# dsPIC_reciver_sch.net
KiCad netlist of a schematic drawn in Altium Designer
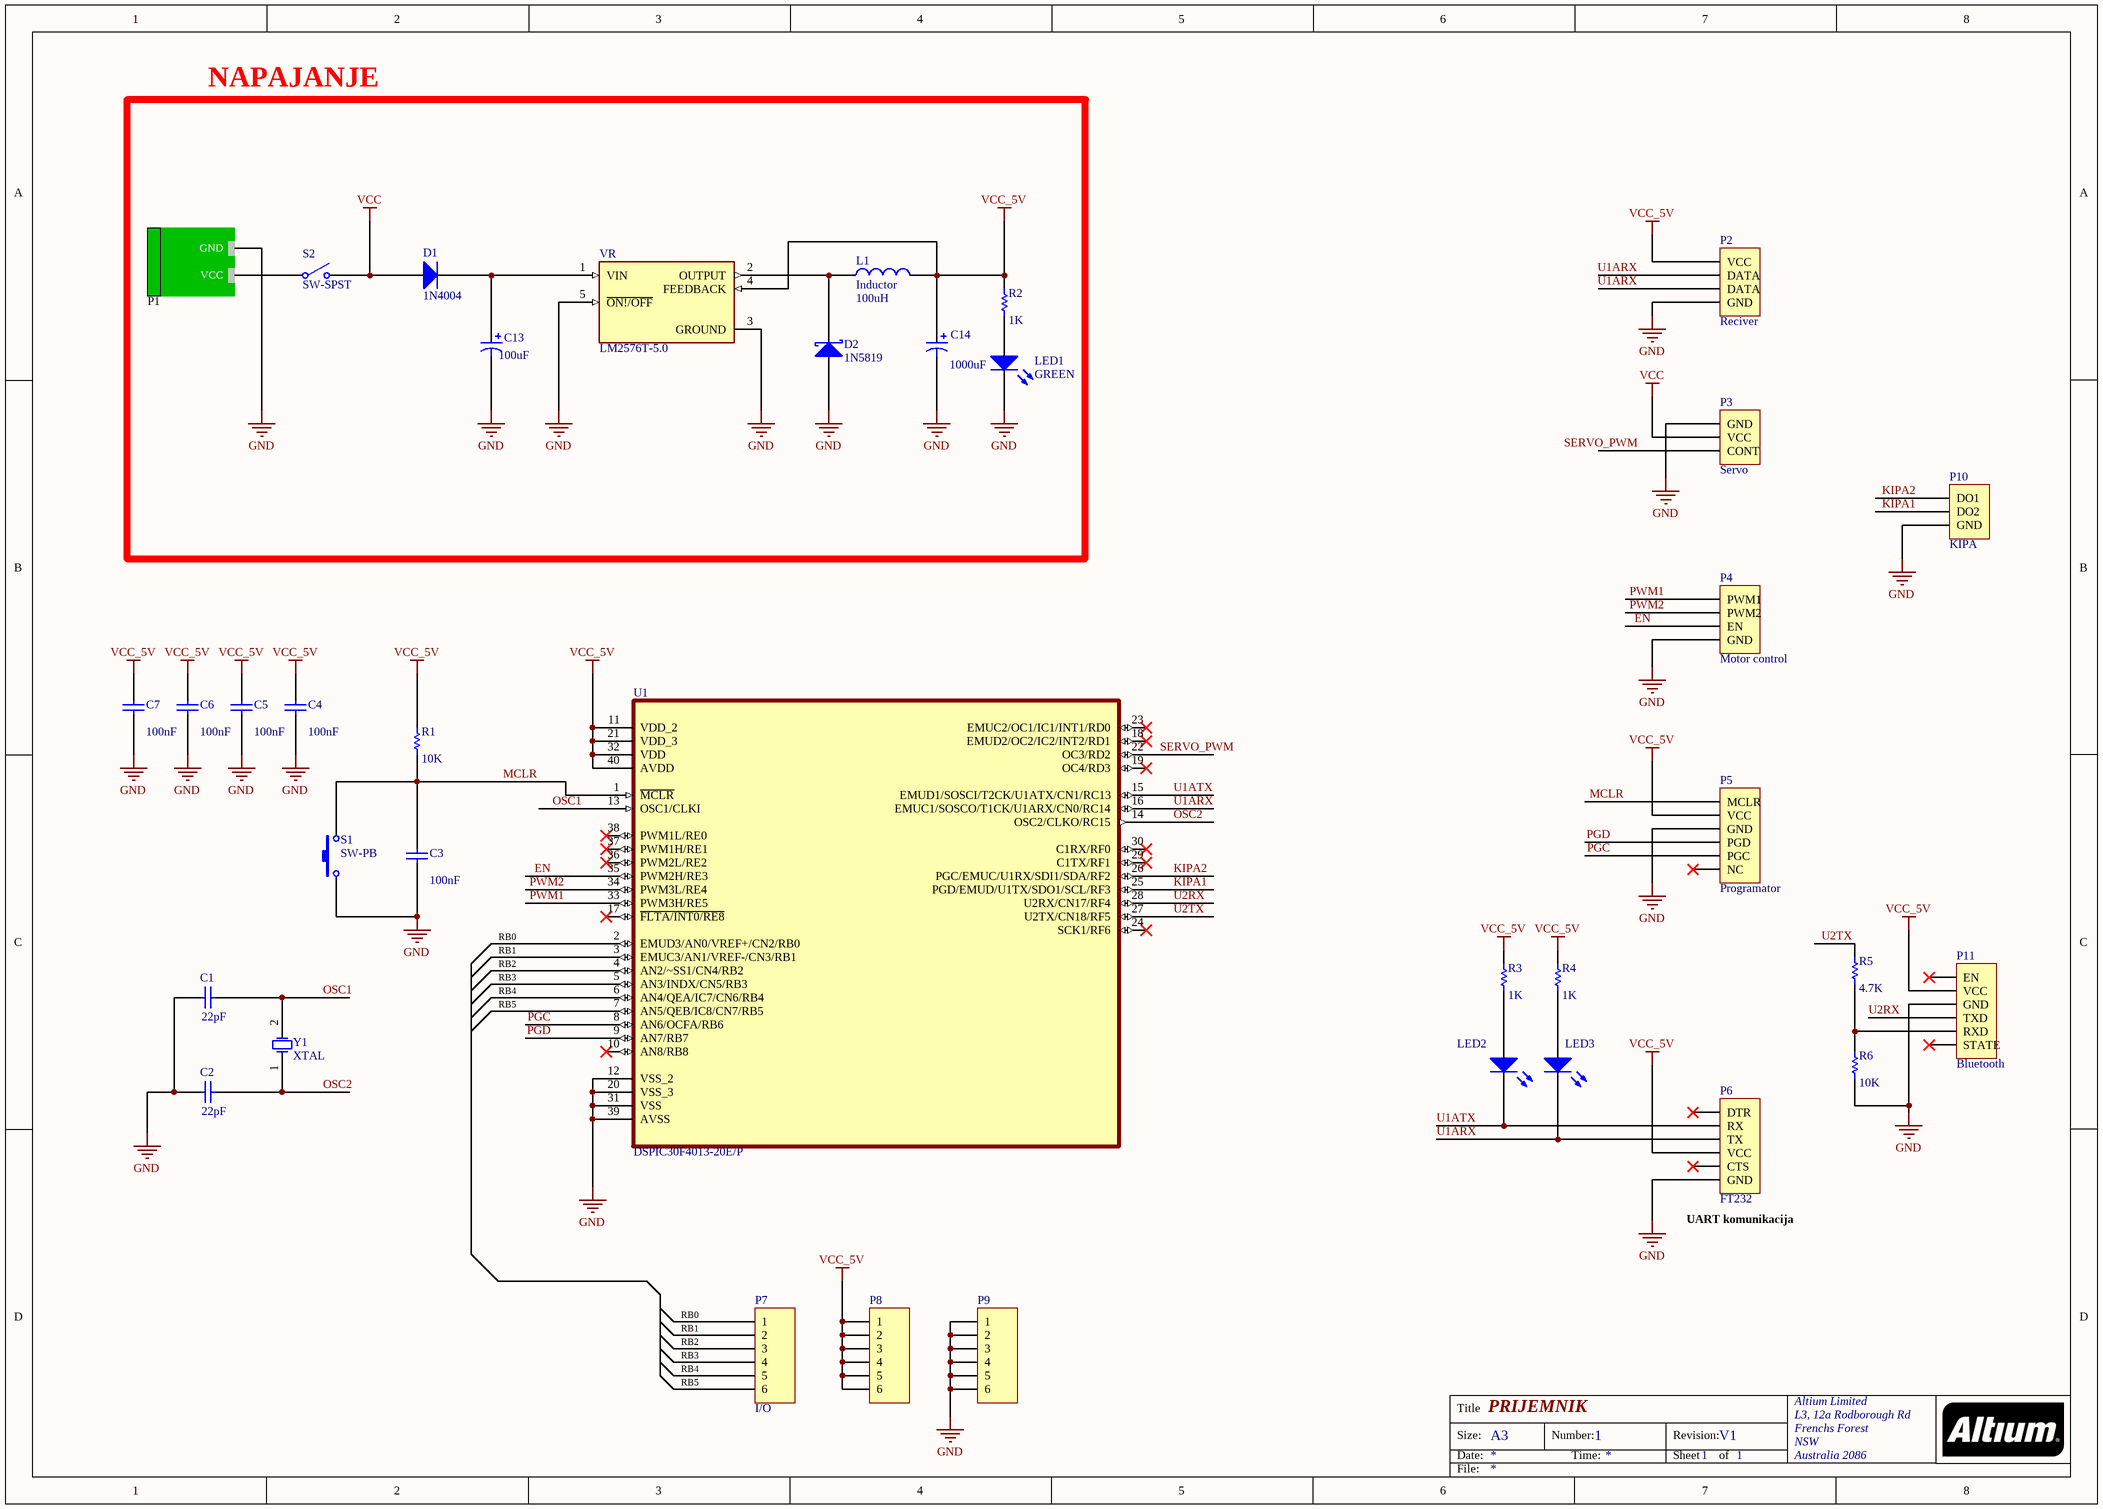
[diagram p0: dsPIC_reciver_sch.SchDoc]

(export (version "E")
  (design (tool "Eeschema 10.0.6"))
  (components
    (comp (ref "C1")
      (value "22pF")
      (footprint "CAP200")
      (description "Capacitor")
      (fields (field (name "Comment") "Cap") (field (name "PUBLISHER") "Altium Limited"))
      (libsource (lib "Miscellaneous Devices") (part "Cap"))
    )
    (comp (ref "C2")
      (value "22pF")
      (footprint "CAP200")
      (description "Capacitor")
      (fields (field (name "Comment") "Cap") (field (name "PUBLISHER") "Altium Limited"))
      (libsource (lib "Miscellaneous Devices") (part "Cap"))
    )
    (comp (ref "C3")
      (value "100nF")
      (footprint "CAP200")
      (description "Capacitor")
      (fields (field (name "Comment") "Cap") (field (name "PUBLISHER") "Altium Limited"))
      (libsource (lib "Miscellaneous Devices") (part "Cap"))
    )
    (comp (ref "C4")
      (value "100nF")
      (footprint "CAP200")
      (description "Capacitor")
      (fields (field (name "Comment") "Cap") (field (name "PUBLISHER") "Altium Limited"))
      (libsource (lib "Miscellaneous Devices") (part "Cap"))
    )
    (comp (ref "C5")
      (value "100nF")
      (footprint "CAP200")
      (description "Capacitor")
      (fields (field (name "Comment") "Cap") (field (name "PUBLISHER") "Altium Limited"))
      (libsource (lib "Miscellaneous Devices") (part "Cap"))
    )
    (comp (ref "C6")
      (value "100nF")
      (footprint "CAP200")
      (description "Capacitor")
      (fields (field (name "Comment") "Cap") (field (name "PUBLISHER") "Altium Limited"))
      (libsource (lib "Miscellaneous Devices") (part "Cap"))
    )
    (comp (ref "C7")
      (value "100nF")
      (footprint "CAP200")
      (description "Capacitor")
      (fields (field (name "Comment") "Cap") (field (name "PUBLISHER") "Altium Limited"))
      (libsource (lib "Miscellaneous Devices") (part "Cap"))
    )
    (comp (ref "C13")
      (value "100uF")
      (footprint "RAD4")
      (description "Polarized Capacitor (Radial)")
      (fields (field (name "Comment") "Cap Pol1") (field (name "PUBLISHER") "Altium Limited"))
      (libsource (lib "Miscellaneous Devices") (part "Cap Pol1"))
    )
    (comp (ref "C14")
      (value "1000uF")
      (footprint "RAD6_3")
      (description "Polarized Capacitor (Radial)")
      (fields (field (name "Comment") "Cap Pol1") (field (name "PUBLISHER") "Altium Limited"))
      (libsource (lib "Miscellaneous Devices") (part "Cap Pol1"))
    )
    (comp (ref "D1")
      (value "1N4004")
      (footprint "DIODE400")
      (description "1 Amp General Purpose Rectifier")
      (fields (field (name "PUBLISHER") "Altium Limited"))
      (libsource (lib "Miscellaneous Devices") (part "Diode 1N4004"))
    )
    (comp (ref "D2")
      (value "1N5819")
      (footprint "SDIODE300")
      (description "Schottky Diode")
      (fields (field (name "PUBLISHER") "Altium Limited"))
      (libsource (lib "Miscellaneous Devices") (part "D Schottky"))
    )
    (comp (ref "L1")
      (value "Inductor")
      (footprint "INDUCTOR_9")
      (fields (field (name "ALTIUM_VALUE") "100uH") (field (name "PUBLISHER") "Altium Limited"))
      (libsource (lib "Miscellaneous Devices") (part "Inductor"))
    )
    (comp (ref "LED1")
      (value "GREEN")
      (footprint "LED_2")
      (description "Typical RED GaAs LED")
      (fields (field (name "PUBLISHER") "Altium Limited"))
      (libsource (lib "Miscellaneous Devices") (part "LED1"))
    )
    (comp (ref "LED2")
      (value "GREEN")
      (footprint "LED_2")
      (description "Typical RED GaAs LED")
      (fields (field (name "PUBLISHER") "Altium Limited"))
      (libsource (lib "Miscellaneous Devices") (part "LED1"))
    )
    (comp (ref "LED3")
      (value "GREEN")
      (footprint "LED_2")
      (description "Typical RED GaAs LED")
      (fields (field (name "PUBLISHER") "Altium Limited"))
      (libsource (lib "Miscellaneous Devices") (part "LED1"))
    )
    (comp (ref "P1")
      (value "2EDGRC-5.08-02P-14-00A(H)")
      (footprint "PWR_Con")
      (description "TERM BLOCK HDR 2POS 90DEG 5.08MM")
      (libsource (lib "Electro_Mechanical") (part "00000002"))
    )
    (comp (ref "P2")
      (value "Reciver")
      (footprint "HEADER_4")
      (description "Header, 4-Pin")
      (fields (field (name "PUBLISHER") "Altium Limited"))
      (libsource (lib "Miscellaneous Connectors") (part "Header 4"))
    )
    (comp (ref "P3")
      (value "Servo")
      (footprint "HEADER_3")
      (description "Header, 3-Pin")
      (fields (field (name "PUBLISHER") "Altium Limited"))
      (libsource (lib "Miscellaneous Connectors") (part "Header 3"))
    )
    (comp (ref "P4")
      (value "Motor control")
      (footprint "HEADER_4")
      (description "Header, 4-Pin")
      (fields (field (name "PUBLISHER") "Altium Limited"))
      (libsource (lib "Miscellaneous Connectors") (part "Header 4"))
    )
    (comp (ref "P5")
      (value "Programator")
      (footprint "HEADER_6")
      (description "Header, 6-Pin")
      (fields (field (name "PUBLISHER") "Altium Limited"))
      (libsource (lib "Miscellaneous Connectors") (part "Header 6"))
    )
    (comp (ref "P6")
      (value "FT232")
      (footprint "HEADER_6")
      (description "Header, 6-Pin")
      (fields (field (name "PUBLISHER") "Altium Limited"))
      (libsource (lib "Miscellaneous Connectors") (part "Header 6"))
    )
    (comp (ref "P7")
      (value "I/O")
      (footprint "HEADER_6")
      (description "Header, 6-Pin")
      (fields (field (name "PUBLISHER") "Altium Limited"))
      (libsource (lib "Miscellaneous Connectors") (part "Header 6"))
    )
    (comp (ref "P8")
      (value "Header 6")
      (footprint "HEADER_6")
      (description "Header, 6-Pin")
      (fields (field (name "PUBLISHER") "Altium Limited"))
      (libsource (lib "Miscellaneous Connectors") (part "Header 6"))
    )
    (comp (ref "P9")
      (value "Header 6")
      (footprint "HEADER_6")
      (description "Header, 6-Pin")
      (fields (field (name "PUBLISHER") "Altium Limited"))
      (libsource (lib "Miscellaneous Connectors") (part "Header 6"))
    )
    (comp (ref "P10")
      (value "KIPA")
      (footprint "HEADER_3")
      (description "Header, 3-Pin")
      (fields (field (name "PUBLISHER") "Altium Limited"))
      (libsource (lib "Miscellaneous Connectors") (part "Header 3"))
    )
    (comp (ref "P11")
      (value "Bluetooth")
      (footprint "HEADER_6")
      (description "Header, 6-Pin")
      (fields (field (name "PUBLISHER") "Altium Limited"))
      (libsource (lib "Miscellaneous Connectors") (part "Header 6"))
    )
    (comp (ref "R1")
      (value "10K")
      (footprint "RES400")
      (description "Resistor")
      (fields (field (name "Comment") "Res1") (field (name "PUBLISHER") "Altium Limited"))
      (libsource (lib "Miscellaneous Devices") (part "Res1"))
    )
    (comp (ref "R2")
      (value "1K")
      (footprint "RES400")
      (description "Resistor")
      (fields (field (name "Comment") "Res1") (field (name "PUBLISHER") "Altium Limited"))
      (libsource (lib "Miscellaneous Devices") (part "Res1"))
    )
    (comp (ref "R3")
      (value "1K")
      (footprint "RES400")
      (description "Resistor")
      (fields (field (name "Comment") "Res1") (field (name "PUBLISHER") "Altium Limited"))
      (libsource (lib "Miscellaneous Devices") (part "Res1"))
    )
    (comp (ref "R4")
      (value "1K")
      (footprint "RES400")
      (description "Resistor")
      (fields (field (name "Comment") "Res1") (field (name "PUBLISHER") "Altium Limited"))
      (libsource (lib "Miscellaneous Devices") (part "Res1"))
    )
    (comp (ref "R5")
      (value "4.7K")
      (footprint "RES400")
      (description "Resistor")
      (fields (field (name "Comment") "Res1") (field (name "PUBLISHER") "Altium Limited"))
      (libsource (lib "Miscellaneous Devices") (part "Res1"))
    )
    (comp (ref "R6")
      (value "10K")
      (footprint "RES400")
      (description "Resistor")
      (fields (field (name "Comment") "Res1") (field (name "PUBLISHER") "Altium Limited"))
      (libsource (lib "Miscellaneous Devices") (part "Res1"))
    )
    (comp (ref "S1")
      (value "SW-PB")
      (footprint "SPST-2")
      (description "Switch")
      (fields (field (name "PUBLISHER") "Altium Limited"))
      (libsource (lib "Miscellaneous Devices") (part "SW-PB"))
    )
    (comp (ref "S2")
      (value "SW-SPST")
      (footprint "CAP200")
      (description "Single-Pole, Single-Throw Switch")
      (fields (field (name "PUBLISHER") "Altium Limited"))
      (libsource (lib "Miscellaneous Devices") (part "SW-SPST"))
    )
    (comp (ref "U1")
      (value "DSPIC30F4013-20E/P")
      (footprint "DIP_40")
      (description "dsPIC dsPICâ„¢ 30F Microcontroller IC 16-Bit 20 MIPS 48KB _16K x 24_ FLASH 40-PDIP")
      (fields (field (name "MF") "Microchip") (field (name "DIGI-KEY_PART_NUMBER") "DSPIC30F4013-20EP-ND"))
      (libsource (lib "DSPIC30F4013-20E_P") (part "DSPIC30F4013-20E/P"))
    )
    (comp (ref "VR")
      (value "LM2576T-5.0")
      (footprint "TO170P1067X483X1651-5")
      (description "Conv DC-DC 4V to 40V Inv/Step Down Single-Out 5V 3A 5-Pin(5+Tab) TO-220 Tube")
      (fields
        (field (name "MF") "HTC Korea")
        (field (name "BUYPART") "https://www.snapeda.com/parts/LM2576T-5.0/HTC%20Korea/view-part/4830195/?ref=eda")
      )
      (libsource (lib "LM2576T-5.0") (part "LM2576T-5.0"))
    )
    (comp (ref "Y1")
      (value "XTAL")
      (footprint "OSC_5")
      (description "Crystal Oscillator")
      (fields (field (name "PUBLISHER") "Altium Limited"))
      (libsource (lib "Miscellaneous Devices") (part "XTAL"))
    )
  )
  (nets
    (net (code "1") (name "/EN") (class "Default")
      (node (ref "P4") (pin "3") (pinfunction "DATA_3") (pintype "passive"))
      (node (ref "U1") (pin "35") (pinfunction "PWM2H/RE3_35") (pintype "bidirectional"))
    )
    (net (code "2") (name "/KIPA1") (class "Default")
      (node (ref "P10") (pin "2") (pinfunction "VCC_2") (pintype "passive"))
      (node (ref "U1") (pin "25") (pinfunction "PGD/EMUD/U1TX/SDO1/SCL/RF3_25") (pintype "bidirectional"))
    )
    (net (code "3") (name "/KIPA2") (class "Default")
      (node (ref "P10") (pin "1") (pinfunction "GND_1") (pintype "passive"))
      (node (ref "U1") (pin "26") (pinfunction "PGC/EMUC/U1RX/SDI1/SDA/RF2_26") (pintype "bidirectional"))
    )
    (net (code "4") (name "/MCLR") (class "Default")
      (node (ref "C3") (pin "2") (pinfunction "2_2") (pintype "passive"))
      (node (ref "P5") (pin "1") (pinfunction "DTR_1") (pintype "passive"))
      (node (ref "R1") (pin "1") (pinfunction "1_1") (pintype "passive"))
      (node (ref "S1") (pin "2") (pinfunction "2_2") (pintype "passive"))
      (node (ref "U1") (pin "1") (pinfunction "~{MCLR}_1") (pintype "input"))
    )
    (net (code "5") (name "/OSC1") (class "Default")
      (node (ref "C1") (pin "2") (pinfunction "2_2") (pintype "passive"))
      (node (ref "U1") (pin "13") (pinfunction "OSC1/CLKI_13") (pintype "input"))
      (node (ref "Y1") (pin "2") (pinfunction "OSC2_2") (pintype "passive"))
    )
    (net (code "6") (name "/OSC2") (class "Default")
      (node (ref "C2") (pin "2") (pinfunction "2_2") (pintype "passive"))
      (node (ref "U1") (pin "14") (pinfunction "OSC2/CLKO/RC15_14") (pintype "output"))
      (node (ref "Y1") (pin "1") (pinfunction "OSC1_1") (pintype "passive"))
    )
    (net (code "7") (name "/PGC") (class "Default")
      (node (ref "P5") (pin "5") (pinfunction "CTS_5") (pintype "passive"))
      (node (ref "U1") (pin "8") (pinfunction "AN6/OCFA/RB6_8") (pintype "bidirectional"))
    )
    (net (code "8") (name "/PGD") (class "Default")
      (node (ref "P5") (pin "4") (pinfunction "VCC_4") (pintype "passive"))
      (node (ref "U1") (pin "9") (pinfunction "AN7/RB7_9") (pintype "bidirectional"))
    )
    (net (code "9") (name "/PWM1") (class "Default")
      (node (ref "P4") (pin "1") (pinfunction "VCC_1") (pintype "passive"))
      (node (ref "U1") (pin "33") (pinfunction "PWM3H/RE5_33") (pintype "bidirectional"))
    )
    (net (code "10") (name "/PWM2") (class "Default")
      (node (ref "P4") (pin "2") (pinfunction "DATA_2") (pintype "passive"))
      (node (ref "U1") (pin "34") (pinfunction "PWM3L/RE4_34") (pintype "bidirectional"))
    )
    (net (code "11") (name "/RB0") (class "Default")
      (node (ref "P7") (pin "1") (pinfunction "DTR_1") (pintype "passive"))
      (node (ref "U1") (pin "2") (pinfunction "EMUD3/AN0/VREF+/CN2/RB0_2") (pintype "bidirectional"))
    )
    (net (code "12") (name "/RB1") (class "Default")
      (node (ref "P7") (pin "2") (pinfunction "RX_2") (pintype "passive"))
      (node (ref "U1") (pin "3") (pinfunction "EMUC3/AN1/VREF-/CN3/RB1_3") (pintype "bidirectional"))
    )
    (net (code "13") (name "/RB2") (class "Default")
      (node (ref "P7") (pin "3") (pinfunction "TX_3") (pintype "passive"))
      (node (ref "U1") (pin "4") (pinfunction "AN2/~SS1/CN4/RB2_4") (pintype "bidirectional"))
    )
    (net (code "14") (name "/RB3") (class "Default")
      (node (ref "P7") (pin "4") (pinfunction "VCC_4") (pintype "passive"))
      (node (ref "U1") (pin "5") (pinfunction "AN3/INDX/CN5/RB3_5") (pintype "bidirectional"))
    )
    (net (code "15") (name "/RB4") (class "Default")
      (node (ref "P7") (pin "5") (pinfunction "CTS_5") (pintype "passive"))
      (node (ref "U1") (pin "6") (pinfunction "AN4/QEA/IC7/CN6/RB4_6") (pintype "bidirectional"))
    )
    (net (code "16") (name "/RB5") (class "Default")
      (node (ref "P7") (pin "6") (pinfunction "GND_6") (pintype "passive"))
      (node (ref "U1") (pin "7") (pinfunction "AN5/QEB/IC8/CN7/RB5_7") (pintype "bidirectional"))
    )
    (net (code "17") (name "/SERVO_PWM") (class "Default")
      (node (ref "P3") (pin "3") (pinfunction "CONT_3") (pintype "passive"))
      (node (ref "U1") (pin "22") (pinfunction "OC3/RD2_22") (pintype "bidirectional"))
    )
    (net (code "18") (name "/U1ARX") (class "Default")
      (node (ref "LED3") (pin "2") (pinfunction "K_2") (pintype "passive"))
      (node (ref "P2") (pin "2") (pinfunction "DATA_2") (pintype "passive"))
      (node (ref "P2") (pin "3") (pinfunction "DATA_3") (pintype "passive"))
      (node (ref "P6") (pin "3") (pinfunction "TX_3") (pintype "passive"))
      (node (ref "U1") (pin "16") (pinfunction "EMUC1/SOSCO/T1CK/U1ARX/CN0/RC14_16") (pintype "bidirectional"))
    )
    (net (code "19") (name "/U1ATX") (class "Default")
      (node (ref "LED2") (pin "2") (pinfunction "K_2") (pintype "passive"))
      (node (ref "P6") (pin "2") (pinfunction "RX_2") (pintype "passive"))
      (node (ref "U1") (pin "15") (pinfunction "EMUD1/SOSCI/T2CK/U1ATX/CN1/RC13_15") (pintype "bidirectional"))
    )
    (net (code "20") (name "/U2RX") (class "Default")
      (node (ref "P11") (pin "4") (pinfunction "VCC_4") (pintype "passive"))
      (node (ref "U1") (pin "28") (pinfunction "U2RX/CN17/RF4_28") (pintype "bidirectional"))
    )
    (net (code "21") (name "/U2TX") (class "Default")
      (node (ref "R5") (pin "2") (pinfunction "2_2") (pintype "passive"))
      (node (ref "U1") (pin "27") (pinfunction "U2TX/CN18/RF5_27") (pintype "bidirectional"))
    )
    (net (code "22") (name "GND") (class "Default")
      (node (ref "C1") (pin "1") (pinfunction "1_1") (pintype "passive"))
      (node (ref "C13") (pin "2") (pinfunction "2_2") (pintype "passive"))
      (node (ref "C14") (pin "2") (pinfunction "2_2") (pintype "passive"))
      (node (ref "C2") (pin "1") (pinfunction "1_1") (pintype "passive"))
      (node (ref "C3") (pin "1") (pinfunction "1_1") (pintype "passive"))
      (node (ref "C4") (pin "1") (pinfunction "1_1") (pintype "passive"))
      (node (ref "C5") (pin "1") (pinfunction "1_1") (pintype "passive"))
      (node (ref "C6") (pin "1") (pinfunction "1_1") (pintype "passive"))
      (node (ref "C7") (pin "1") (pinfunction "1_1") (pintype "passive"))
      (node (ref "D2") (pin "1") (pinfunction "A_1") (pintype "passive"))
      (node (ref "LED1") (pin "2") (pinfunction "K_2") (pintype "passive"))
      (node (ref "P1") (pin "1") (pinfunction "GND_1") (pintype "passive"))
      (node (ref "P10") (pin "3") (pinfunction "CONT_3") (pintype "passive"))
      (node (ref "P11") (pin "3") (pinfunction "TX_3") (pintype "passive"))
      (node (ref "P2") (pin "4") (pinfunction "GND_4") (pintype "passive"))
      (node (ref "P3") (pin "1") (pinfunction "GND_1") (pintype "passive"))
      (node (ref "P4") (pin "4") (pinfunction "GND_4") (pintype "passive"))
      (node (ref "P5") (pin "3") (pinfunction "TX_3") (pintype "passive"))
      (node (ref "P6") (pin "6") (pinfunction "GND_6") (pintype "passive"))
      (node (ref "P9") (pin "1") (pinfunction "DTR_1") (pintype "passive"))
      (node (ref "P9") (pin "2") (pinfunction "RX_2") (pintype "passive"))
      (node (ref "P9") (pin "3") (pinfunction "TX_3") (pintype "passive"))
      (node (ref "P9") (pin "4") (pinfunction "VCC_4") (pintype "passive"))
      (node (ref "P9") (pin "5") (pinfunction "CTS_5") (pintype "passive"))
      (node (ref "P9") (pin "6") (pinfunction "GND_6") (pintype "passive"))
      (node (ref "R6") (pin "1") (pinfunction "1_1") (pintype "passive"))
      (node (ref "S1") (pin "1") (pinfunction "1_1") (pintype "passive"))
      (node (ref "U1") (pin "12") (pinfunction "VSS_2_12") (pintype "power_in"))
      (node (ref "U1") (pin "20") (pinfunction "VSS_3_20") (pintype "power_in"))
      (node (ref "U1") (pin "31") (pinfunction "VSS_31") (pintype "power_in"))
      (node (ref "U1") (pin "39") (pinfunction "AVSS_39") (pintype "power_in"))
      (node (ref "VR") (pin "3") (pinfunction "GROUND_3") (pintype "power_in"))
      (node (ref "VR") (pin "5") (pinfunction "~{ON!/OFF}_5") (pintype "input"))
    )
    (net (code "23") (name "Net-(D1-K)") (class "Default")
      (node (ref "C13") (pin "1") (pinfunction "1_1") (pintype "passive"))
      (node (ref "D1") (pin "2") (pinfunction "K_2") (pintype "passive"))
      (node (ref "VR") (pin "1") (pinfunction "VIN_1") (pintype "input"))
    )
    (net (code "24") (name "Net-(D2-K)") (class "Default")
      (node (ref "D2") (pin "2") (pinfunction "K_2") (pintype "passive"))
      (node (ref "L1") (pin "1") (pinfunction "1_1") (pintype "passive"))
      (node (ref "VR") (pin "2") (pinfunction "OUTPUT_2") (pintype "output"))
    )
    (net (code "25") (name "Net-(LED1-A)") (class "Default")
      (node (ref "LED1") (pin "1") (pinfunction "A_1") (pintype "passive"))
      (node (ref "R2") (pin "1") (pinfunction "1_1") (pintype "passive"))
    )
    (net (code "26") (name "Net-(LED2-A)") (class "Default")
      (node (ref "LED2") (pin "1") (pinfunction "A_1") (pintype "passive"))
      (node (ref "R3") (pin "1") (pinfunction "1_1") (pintype "passive"))
    )
    (net (code "27") (name "Net-(LED3-A)") (class "Default")
      (node (ref "LED3") (pin "1") (pinfunction "A_1") (pintype "passive"))
      (node (ref "R4") (pin "1") (pinfunction "1_1") (pintype "passive"))
    )
    (net (code "28") (name "Net-(P1-VCC)") (class "Default")
      (node (ref "P1") (pin "2") (pinfunction "VCC_2") (pintype "passive"))
      (node (ref "S2") (pin "1") (pinfunction "COMMON_1") (pintype "passive"))
    )
    (net (code "29") (name "Net-(P11-CTS)") (class "Default")
      (node (ref "P11") (pin "5") (pinfunction "CTS_5") (pintype "passive"))
      (node (ref "R5") (pin "1") (pinfunction "1_1") (pintype "passive"))
      (node (ref "R6") (pin "2") (pinfunction "2_2") (pintype "passive"))
    )
    (net (code "30") (name "VCC") (class "Default")
      (node (ref "D1") (pin "1") (pinfunction "A_1") (pintype "passive"))
      (node (ref "P3") (pin "2") (pinfunction "VCC_2") (pintype "passive"))
      (node (ref "S2") (pin "2") (pinfunction "NO_2") (pintype "passive"))
    )
    (net (code "31") (name "VCC_5V") (class "Default")
      (node (ref "C14") (pin "1") (pinfunction "1_1") (pintype "passive"))
      (node (ref "C4") (pin "2") (pinfunction "2_2") (pintype "passive"))
      (node (ref "C5") (pin "2") (pinfunction "2_2") (pintype "passive"))
      (node (ref "C6") (pin "2") (pinfunction "2_2") (pintype "passive"))
      (node (ref "C7") (pin "2") (pinfunction "2_2") (pintype "passive"))
      (node (ref "L1") (pin "2") (pinfunction "2_2") (pintype "passive"))
      (node (ref "P11") (pin "2") (pinfunction "RX_2") (pintype "passive"))
      (node (ref "P2") (pin "1") (pinfunction "VCC_1") (pintype "passive"))
      (node (ref "P5") (pin "2") (pinfunction "RX_2") (pintype "passive"))
      (node (ref "P6") (pin "4") (pinfunction "VCC_4") (pintype "passive"))
      (node (ref "P8") (pin "1") (pinfunction "DTR_1") (pintype "passive"))
      (node (ref "P8") (pin "2") (pinfunction "RX_2") (pintype "passive"))
      (node (ref "P8") (pin "3") (pinfunction "TX_3") (pintype "passive"))
      (node (ref "P8") (pin "4") (pinfunction "VCC_4") (pintype "passive"))
      (node (ref "P8") (pin "5") (pinfunction "CTS_5") (pintype "passive"))
      (node (ref "P8") (pin "6") (pinfunction "GND_6") (pintype "passive"))
      (node (ref "R1") (pin "2") (pinfunction "2_2") (pintype "passive"))
      (node (ref "R2") (pin "2") (pinfunction "2_2") (pintype "passive"))
      (node (ref "R3") (pin "2") (pinfunction "2_2") (pintype "passive"))
      (node (ref "R4") (pin "2") (pinfunction "2_2") (pintype "passive"))
      (node (ref "U1") (pin "11") (pinfunction "VDD_2_11") (pintype "power_in"))
      (node (ref "U1") (pin "21") (pinfunction "VDD_3_21") (pintype "power_in"))
      (node (ref "U1") (pin "32") (pinfunction "VDD_32") (pintype "power_in"))
      (node (ref "U1") (pin "40") (pinfunction "AVDD_40") (pintype "power_in"))
      (node (ref "VR") (pin "4") (pinfunction "FEEDBACK_4") (pintype "input"))
    )
    (net (code "32") (name "unconnected-(P5-GND-Pad6)") (class "Default")
      (node (ref "P5") (pin "6") (pinfunction "GND_6") (pintype "passive+no_connect"))
    )
    (net (code "33") (name "unconnected-(P6-CTS-Pad5)") (class "Default")
      (node (ref "P6") (pin "5") (pinfunction "CTS_5") (pintype "passive+no_connect"))
    )
    (net (code "34") (name "unconnected-(P6-DTR-Pad1)") (class "Default")
      (node (ref "P6") (pin "1") (pinfunction "DTR_1") (pintype "passive+no_connect"))
    )
    (net (code "35") (name "unconnected-(P11-DTR-Pad1)") (class "Default")
      (node (ref "P11") (pin "1") (pinfunction "DTR_1") (pintype "passive+no_connect"))
    )
    (net (code "36") (name "unconnected-(P11-GND-Pad6)") (class "Default")
      (node (ref "P11") (pin "6") (pinfunction "GND_6") (pintype "passive+no_connect"))
    )
    (net (code "37") (name "unconnected-(U1-AN8{slash}RB8-Pad10)") (class "Default")
      (node (ref "U1") (pin "10") (pinfunction "AN8/RB8_10") (pintype "bidirectional+no_connect"))
    )
    (net (code "38") (name "unconnected-(U1-C1RX{slash}RF0-Pad30)") (class "Default")
      (node (ref "U1") (pin "30") (pinfunction "C1RX/RF0_30") (pintype "bidirectional+no_connect"))
    )
    (net (code "39") (name "unconnected-(U1-C1TX{slash}RF1-Pad29)") (class "Default")
      (node (ref "U1") (pin "29") (pinfunction "C1TX/RF1_29") (pintype "bidirectional+no_connect"))
    )
    (net (code "40") (name "unconnected-(U1-EMUC2{slash}OC1{slash}IC1{slash}INT1{slash}RD0-Pad23)") (class "Default")
      (node (ref "U1") (pin "23") (pinfunction "EMUC2/OC1/IC1/INT1/RD0_23") (pintype "bidirectional+no_connect"))
    )
    (net (code "41") (name "unconnected-(U1-EMUD2{slash}OC2{slash}IC2{slash}INT2{slash}RD1-Pad18)") (class "Default")
      (node (ref "U1") (pin "18") (pinfunction "EMUD2/OC2/IC2/INT2/RD1_18") (pintype "bidirectional+no_connect"))
    )
    (net (code "42") (name "unconnected-(U1-OC4{slash}RD3-Pad19)") (class "Default")
      (node (ref "U1") (pin "19") (pinfunction "OC4/RD3_19") (pintype "bidirectional+no_connect"))
    )
    (net (code "43") (name "unconnected-(U1-PWM1H{slash}RE1-Pad37)") (class "Default")
      (node (ref "U1") (pin "37") (pinfunction "PWM1H/RE1_37") (pintype "bidirectional+no_connect"))
    )
    (net (code "44") (name "unconnected-(U1-PWM1L{slash}RE0-Pad38)") (class "Default")
      (node (ref "U1") (pin "38") (pinfunction "PWM1L/RE0_38") (pintype "bidirectional+no_connect"))
    )
    (net (code "45") (name "unconnected-(U1-PWM2L{slash}RE2-Pad36)") (class "Default")
      (node (ref "U1") (pin "36") (pinfunction "PWM2L/RE2_36") (pintype "bidirectional+no_connect"))
    )
    (net (code "46") (name "unconnected-(U1-SCK1{slash}RF6-Pad24)") (class "Default")
      (node (ref "U1") (pin "24") (pinfunction "SCK1/RF6_24") (pintype "bidirectional+no_connect"))
    )
    (net (code "47") (name "unconnected-(U1-~{FLTA{slash}INT0{slash}RE8}-Pad17)") (class "Default")
      (node (ref "U1") (pin "17") (pinfunction "~{FLTA/INT0/RE8}_17") (pintype "bidirectional+no_connect"))
    )
  )
)
